# Sheet2.net
KiCad netlist of a schematic drawn in Altium Designer
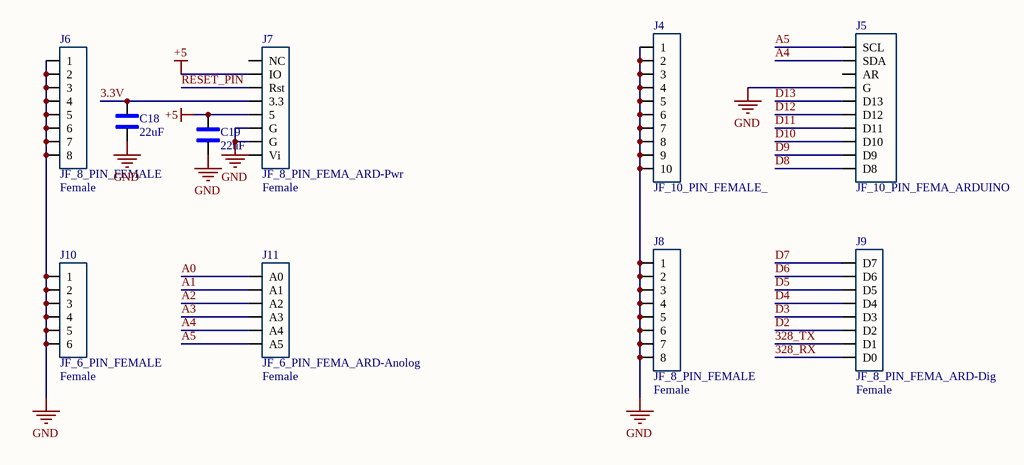
[diagram p0: Sheet2.SchDoc]

(export (version "E")
  (design (tool "Eeschema 10.0.6"))
  (components
    (comp (ref "C18")
      (value "22uF")
      (footprint "1206_Passive_Capacitor")
      (description "22uF ±10% 25V X5R 1206 Multilayer Ceramic Capacitors MLCC - SMD/SMT RoHS")
      (fields (field (name "MFR PART #") "CL31A226KAHNNNE") (field (name "LCSC PART#") "C12891"))
      (libsource (lib "ECEN5730Lib_2023_05_DS") (part "C_22uF_1206"))
    )
    (comp (ref "C19")
      (value "22uF")
      (footprint "1206_Passive_Capacitor")
      (description "22uF ±10% 25V X5R 1206 Multilayer Ceramic Capacitors MLCC - SMD/SMT RoHS")
      (fields (field (name "MFR PART #") "CL31A226KAHNNNE") (field (name "LCSC PART#") "C12891"))
      (libsource (lib "ECEN5730Lib_2023_05_DS") (part "C_22uF_1206"))
    )
    (comp (ref "J4")
      (value "JF_10_PIN_FEMALE_")
      (footprint "10_PIN_100MIL - Female")
      (description "10 Position Header Connector 0.100\" (2.54mm) Through Hole Tin")
      (fields (field (name "LCSC PART#") "C225507") (field (name "MFR PART #") "PPTC101LFBN-RC"))
      (libsource (lib "University of Colorado") (part "JF_10_PIN_FEMALE_"))
    )
    (comp (ref "J5")
      (value "JF_10_PIN_FEMA_ARDUINO")
      (footprint "10_PIN_ARDUINO_100MIL")
      (description "10 Position Header Connector 0.100\" (2.54mm) Through Hole Tin")
      (fields (field (name "LCSC PART#") "C225507") (field (name "MFR PART #") "PPTC101LFBN-RC"))
      (libsource (lib "University of Colorado") (part "JF_10_PIN_FEMA_ARDUINO"))
    )
    (comp (ref "J6")
      (value "JF_8_PIN_FEMALE")
      (footprint "8_PIN_100MIL - Female")
      (description "8 Position Header Connector 0.100\" (2.54mm) Through Hole Tin")
      (fields
        (field (name "ALTIUM_VALUE") "Female")
        (field (name "MFR PART #") "PPTC081LFBN-RC")
        (field (name "LCSC PART#") "C27438")
      )
      (libsource (lib "University of Colorado") (part "JF_8_PIN_FEMALE"))
    )
    (comp (ref "J7")
      (value "JF_8_PIN_FEMA_ARD-Pwr")
      (footprint "8_PIN_ARD-PWR_100MIL")
      (description "8 Position Header Connector 0.100\" (2.54mm) Through Hole Tin")
      (fields
        (field (name "ALTIUM_VALUE") "Female")
        (field (name "LCSC PART#") "C27438")
        (field (name "MFR PART #") "PPTC081LFBN-RC")
      )
      (libsource (lib "University of Colorado") (part "JF_8_PIN_FEMA_ARD-Pwr"))
    )
    (comp (ref "J8")
      (value "JF_8_PIN_FEMALE")
      (footprint "8_PIN_100MIL - Female")
      (description "8 Position Header Connector 0.100\" (2.54mm) Through Hole Tin")
      (fields
        (field (name "ALTIUM_VALUE") "Female")
        (field (name "MFR PART #") "PPTC081LFBN-RC")
        (field (name "LCSC PART#") "C27438")
      )
      (libsource (lib "University of Colorado") (part "JF_8_PIN_FEMALE"))
    )
    (comp (ref "J9")
      (value "JF_8_PIN_FEMA_ARD-Dig")
      (footprint "8_PIN_ARD-DIG_100MIL")
      (description "8 Position Header Connector 0.100\" (2.54mm) Through Hole Tin")
      (fields
        (field (name "ALTIUM_VALUE") "Female")
        (field (name "LCSC PART#") "C27438")
        (field (name "MFR PART #") "PPTC081LFBN-RC")
      )
      (libsource (lib "University of Colorado") (part "JF_8_PIN_FEMA_ARD-Dig"))
    )
    (comp (ref "J10")
      (value "JF_6_PIN_FEMALE")
      (footprint "6_PIN_100MIL -Female")
      (description "6 Position Header Connector 0.100\" (2.54mm) Through Hole Tin")
      (fields
        (field (name "ALTIUM_VALUE") "Female")
        (field (name "LCSC PART#") "C40877")
        (field (name "MFR PART #") "PPTC061LFBN-RC")
      )
      (libsource (lib "University of Colorado") (part "JF_6_PIN_FEMALE"))
    )
    (comp (ref "J11")
      (value "JF_6_PIN_FEMA_ARD-Anolog")
      (footprint "6_PIN_ARD-Analog_100mil")
      (description "6 Position Header Connector 0.100\" (2.54mm) Through Hole Tin")
      (fields
        (field (name "ALTIUM_VALUE") "Female")
        (field (name "LCSC PART#") "C40877")
        (field (name "MFR PART #") "PPTC061LFBN-RC")
      )
      (libsource (lib "University of Colorado") (part "JF_6_PIN_FEMA_ARD-Anolog"))
    )
  )
  (nets
    (net (code "1") (name "+5") (class "Default")
      (node (ref "C19") (pin "2") (pinfunction "2_2") (pintype "passive"))
      (node (ref "J7") (pin "2") (pinfunction "IO_2") (pintype "passive"))
      (node (ref "J7") (pin "5") (pinfunction "5_5") (pintype "passive"))
    )
    (net (code "2") (name "/3.3V") (class "Default")
      (node (ref "C18") (pin "2") (pinfunction "2_2") (pintype "passive"))
      (node (ref "J7") (pin "4") (pinfunction "3.3_4") (pintype "passive"))
    )
    (net (code "3") (name "/328_RX") (class "Default")
      (node (ref "J9") (pin "8") (pinfunction "D0_8") (pintype "passive"))
    )
    (net (code "4") (name "/328_TX") (class "Default")
      (node (ref "J9") (pin "7") (pinfunction "D1_7") (pintype "passive"))
    )
    (net (code "5") (name "/A0") (class "Default")
      (node (ref "J11") (pin "1") (pinfunction "A0_1") (pintype "passive"))
    )
    (net (code "6") (name "/A1") (class "Default")
      (node (ref "J11") (pin "2") (pinfunction "A1_2") (pintype "passive"))
    )
    (net (code "7") (name "/A2") (class "Default")
      (node (ref "J11") (pin "3") (pinfunction "A2_3") (pintype "passive"))
    )
    (net (code "8") (name "/A3") (class "Default")
      (node (ref "J11") (pin "4") (pinfunction "A3_4") (pintype "passive"))
    )
    (net (code "9") (name "/A4") (class "Default")
      (node (ref "J11") (pin "5") (pinfunction "A4_5") (pintype "passive"))
      (node (ref "J5") (pin "2") (pinfunction "SDA_2") (pintype "passive"))
    )
    (net (code "10") (name "/A5") (class "Default")
      (node (ref "J11") (pin "6") (pinfunction "A5_6") (pintype "passive"))
      (node (ref "J5") (pin "1") (pinfunction "SCL_1") (pintype "passive"))
    )
    (net (code "11") (name "/D2") (class "Default")
      (node (ref "J9") (pin "6") (pinfunction "D2_6") (pintype "passive"))
    )
    (net (code "12") (name "/D3") (class "Default")
      (node (ref "J9") (pin "5") (pinfunction "D3_5") (pintype "passive"))
    )
    (net (code "13") (name "/D4") (class "Default")
      (node (ref "J9") (pin "4") (pinfunction "D4_4") (pintype "passive"))
    )
    (net (code "14") (name "/D5") (class "Default")
      (node (ref "J9") (pin "3") (pinfunction "D5_3") (pintype "passive"))
    )
    (net (code "15") (name "/D6") (class "Default")
      (node (ref "J9") (pin "2") (pinfunction "D6_2") (pintype "passive"))
    )
    (net (code "16") (name "/D7") (class "Default")
      (node (ref "J9") (pin "1") (pinfunction "D7_1") (pintype "passive"))
    )
    (net (code "17") (name "/D8") (class "Default")
      (node (ref "J5") (pin "10") (pinfunction "D8_10") (pintype "passive"))
    )
    (net (code "18") (name "/D9") (class "Default")
      (node (ref "J5") (pin "9") (pinfunction "D9_9") (pintype "passive"))
    )
    (net (code "19") (name "/D10") (class "Default")
      (node (ref "J5") (pin "8") (pinfunction "D10_8") (pintype "passive"))
    )
    (net (code "20") (name "/D11") (class "Default")
      (node (ref "J5") (pin "7") (pinfunction "D11_7") (pintype "passive"))
    )
    (net (code "21") (name "/D12") (class "Default")
      (node (ref "J5") (pin "6") (pinfunction "D12_6") (pintype "passive"))
    )
    (net (code "22") (name "/D13") (class "Default")
      (node (ref "J5") (pin "5") (pinfunction "D13_5") (pintype "passive"))
    )
    (net (code "23") (name "/RESET_PIN") (class "Default")
      (node (ref "J7") (pin "3") (pinfunction "Rst_3") (pintype "passive"))
    )
    (net (code "24") (name "GND") (class "Default")
      (node (ref "C18") (pin "1") (pinfunction "1_1") (pintype "passive"))
      (node (ref "C19") (pin "1") (pinfunction "1_1") (pintype "passive"))
      (node (ref "J10") (pin "1") (pinfunction "1_1") (pintype "passive"))
      (node (ref "J10") (pin "2") (pinfunction "2_2") (pintype "passive"))
      (node (ref "J10") (pin "3") (pinfunction "3_3") (pintype "passive"))
      (node (ref "J10") (pin "4") (pinfunction "4_4") (pintype "passive"))
      (node (ref "J10") (pin "5") (pinfunction "5_5") (pintype "passive"))
      (node (ref "J10") (pin "6") (pinfunction "6_6") (pintype "passive"))
      (node (ref "J4") (pin "1") (pinfunction "1_1") (pintype "passive"))
      (node (ref "J4") (pin "10") (pinfunction "10_10") (pintype "passive"))
      (node (ref "J4") (pin "2") (pinfunction "2_2") (pintype "passive"))
      (node (ref "J4") (pin "3") (pinfunction "3_3") (pintype "passive"))
      (node (ref "J4") (pin "4") (pinfunction "4_4") (pintype "passive"))
      (node (ref "J4") (pin "5") (pinfunction "5_5") (pintype "passive"))
      (node (ref "J4") (pin "6") (pinfunction "6_6") (pintype "passive"))
      (node (ref "J4") (pin "7") (pinfunction "7_7") (pintype "passive"))
      (node (ref "J4") (pin "8") (pinfunction "8_8") (pintype "passive"))
      (node (ref "J4") (pin "9") (pinfunction "9_9") (pintype "passive"))
      (node (ref "J5") (pin "4") (pinfunction "G_4") (pintype "passive"))
      (node (ref "J6") (pin "1") (pinfunction "1_1") (pintype "passive"))
      (node (ref "J6") (pin "2") (pinfunction "2_2") (pintype "passive"))
      (node (ref "J6") (pin "3") (pinfunction "3_3") (pintype "passive"))
      (node (ref "J6") (pin "4") (pinfunction "4_4") (pintype "passive"))
      (node (ref "J6") (pin "5") (pinfunction "5_5") (pintype "passive"))
      (node (ref "J6") (pin "6") (pinfunction "6_6") (pintype "passive"))
      (node (ref "J6") (pin "7") (pinfunction "7_7") (pintype "passive"))
      (node (ref "J6") (pin "8") (pinfunction "8_8") (pintype "passive"))
      (node (ref "J7") (pin "6") (pinfunction "G_6") (pintype "passive"))
      (node (ref "J7") (pin "7") (pinfunction "G_7") (pintype "passive"))
      (node (ref "J8") (pin "1") (pinfunction "1_1") (pintype "passive"))
      (node (ref "J8") (pin "2") (pinfunction "2_2") (pintype "passive"))
      (node (ref "J8") (pin "3") (pinfunction "3_3") (pintype "passive"))
      (node (ref "J8") (pin "4") (pinfunction "4_4") (pintype "passive"))
      (node (ref "J8") (pin "5") (pinfunction "5_5") (pintype "passive"))
      (node (ref "J8") (pin "6") (pinfunction "6_6") (pintype "passive"))
      (node (ref "J8") (pin "7") (pinfunction "7_7") (pintype "passive"))
      (node (ref "J8") (pin "8") (pinfunction "8_8") (pintype "passive"))
    )
    (net (code "25") (name "unconnected-(J5-AR-Pad3)") (class "Default")
      (node (ref "J5") (pin "3") (pinfunction "AR_3") (pintype "passive"))
    )
    (net (code "26") (name "unconnected-(J7-NC-Pad1)") (class "Default")
      (node (ref "J7") (pin "1") (pinfunction "NC_1") (pintype "passive"))
    )
    (net (code "27") (name "unconnected-(J7-Vi-Pad8)") (class "Default")
      (node (ref "J7") (pin "8") (pinfunction "Vi_8") (pintype "passive"))
    )
  )
)
